# Serial.net
KiCad netlist of a schematic drawn in Altium Designer
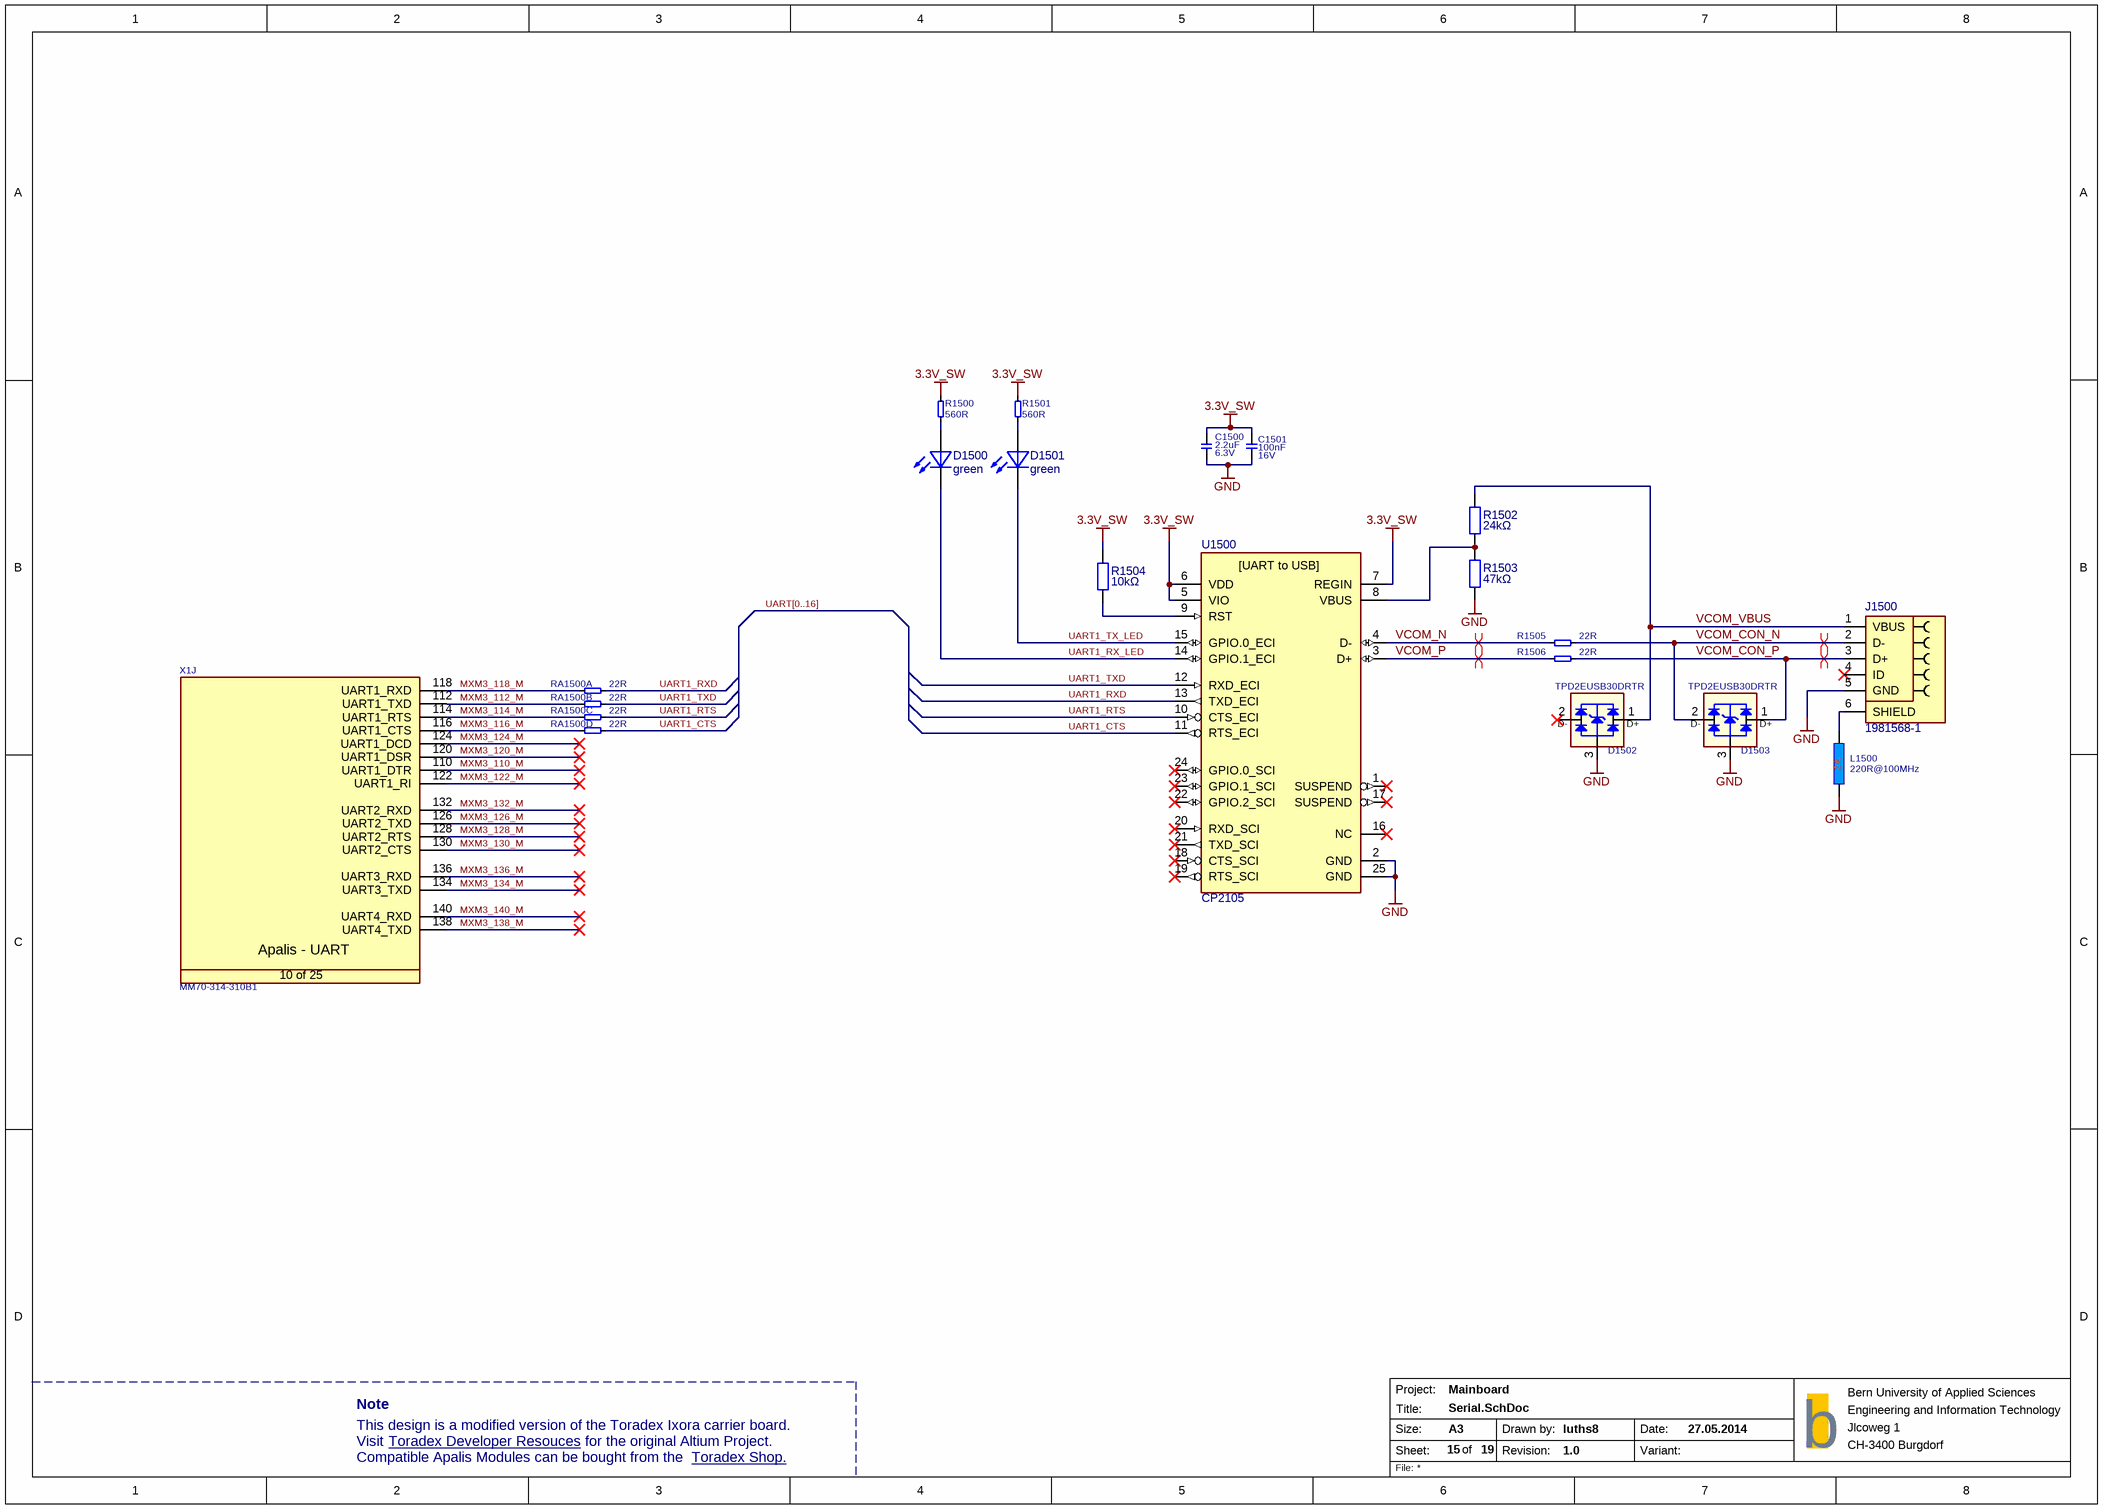
[diagram p0: Serial.SchDoc]

(export (version "E")
  (design (tool "Eeschema 10.0.6"))
  (components
    (comp (ref "C1500")
      (value "2.2uF")
      (footprint "SMD0603CAP")
      (description "Capacitor Ceramic X5R 2.2uF 6.3V 20% 0603")
      (fields (field (name "TOLERANCE") "20%") (field (name "RATING") "6.3V"))
      (libsource (lib "Ixora") (part "C-X5R-2.2uF-6.3V-20%-0603"))
    )
    (comp (ref "C1501")
      (value "100nF")
      (footprint "SMD0603CAP")
      (description "Capacitor Ceramic X7R 100nF 16V 10% 0603")
      (fields (field (name "TOLERANCE") "10%") (field (name "RATING") "16V"))
      (libsource (lib "Ixora") (part "C-X7R-100nF-16V-10%-0402"))
    )
    (comp (ref "D1500")
      (value "green")
      (footprint "LED")
      (description "LED green")
      (fields (field (name "MANUFACTURER PART NO.") "LGM67KG1J224Z"))
      (libsource (lib "Audio-Streamer") (part "LED green"))
    )
    (comp (ref "D1501")
      (value "green")
      (footprint "LED")
      (description "LED green")
      (fields (field (name "MANUFACTURER PART NO.") "LGM67KG1J224Z"))
      (libsource (lib "Audio-Streamer") (part "LED green"))
    )
    (comp (ref "D1502")
      (value "TPD2EUSB30DRTR")
      (footprint "T_TI_TPD2EUSB30DRTR")
      (description "2 Channel Protection for Super Speed USB3.0")
      (fields (field (name "MANUFACTURER PART NO.") "TPD2EUSB30DRTR"))
      (libsource (lib "Ixora") (part "D-TI-TPD2EUSB30DRTR"))
    )
    (comp (ref "D1503")
      (value "TPD2EUSB30DRTR")
      (footprint "T_TI_TPD2EUSB30DRTR")
      (description "2 Channel Protection for Super Speed USB3.0")
      (fields (field (name "MANUFACTURER PART NO.") "TPD2EUSB30DRTR"))
      (libsource (lib "Ixora") (part "D-TI-TPD2EUSB30DRTR"))
    )
    (comp (ref "J1500")
      (value "1981568-1")
      (footprint "HEADER_USB")
      (description "USB Micro Connector")
      (libsource (lib "Audio-Streamer") (part "Connector USB"))
    )
    (comp (ref "L1500")
      (value "220R@100MHz")
      (footprint "INDC1608X95N")
      (description "220R@100MHz 2A EMI FILTER")
      (fields (field (name "TOLERANCE") "25%"))
      (libsource (lib "Ixora") (part "L-220R@100MHz-2A-25%-0603"))
    )
    (comp (ref "R1500")
      (value "560R")
      (footprint "SMD0603RES")
      (description "Resistor 560 ohm 63mW 5% 0603")
      (fields (field (name "TOLERANCE") "5%"))
      (libsource (lib "Ixora") (part "R-560R-63mW-5%-0402"))
    )
    (comp (ref "R1501")
      (value "560R")
      (footprint "SMD0603RES")
      (description "Resistor 560 ohm 63mW 5% 0603")
      (fields (field (name "TOLERANCE") "5%"))
      (libsource (lib "Ixora") (part "R-560R-63mW-5%-0402"))
    )
    (comp (ref "R1502")
      (value "24kΩ")
      (footprint "SMD0603RES")
      (description "Resistor")
      (libsource (lib "Audio-Streamer") (part "Resistor"))
    )
    (comp (ref "R1503")
      (value "47kΩ")
      (footprint "SMD0603RES")
      (description "Resistor")
      (libsource (lib "Audio-Streamer") (part "Resistor"))
    )
    (comp (ref "R1504")
      (value "10kΩ")
      (footprint "SMD0603RES")
      (description "Resistor")
      (libsource (lib "Audio-Streamer") (part "Resistor"))
    )
    (comp (ref "R1505")
      (value "22R")
      (footprint "SMD0603RES")
      (description "Resistor 22 ohm 63mW 5% 0603")
      (fields (field (name "TOLERANCE") "5%"))
      (libsource (lib "Ixora") (part "R-22R-63mW-5%-0402"))
    )
    (comp (ref "R1506")
      (value "22R")
      (footprint "SMD0603RES")
      (description "Resistor 22 ohm 63mW 5% 0603")
      (fields (field (name "TOLERANCE") "5%"))
      (libsource (lib "Ixora") (part "R-22R-63mW-5%-0402"))
    )
    (comp (ref "RA1500")
      (value "22R")
      (footprint "T_Resistor_Array_X4")
      (description "Resistor Array 22 R 63mW 5% 1206")
      (fields (field (name "TOLERANCE") "5%"))
      (libsource (lib "") (part "RA-22R-63mW-5%-1206-div_2"))
    )
    (comp (ref "U1500")
      (value "CP2105")
      (footprint "QFN24")
      (description "USB to UART Bridge")
      (fields (field (name "MANUFACTURER PART NO.") "CP2105-F01-GMR"))
      (libsource (lib "Audio-Streamer") (part "CP2105"))
    )
    (comp (ref "X1")
      (value "CON-JAE-MM70-314-310B1-314-0.5mm")
      (footprint "T_JAE_MM70-314-310B1")
      (description "MXM3 Connector")
      (fields (field (name "MANUFACTURER PART NO.") "MM70-314-310B1"))
      (libsource (lib "Ixora") (part "CON-JAE-MM70-314-310B1-314-0.5mm"))
    )
  )
  (nets
    (net (code "18") (name "/MXM3_110_M") (class "Default")
      (node (ref "X1") (pin "110") (pinfunction "UART1_DTR_110") (pintype "passive+no_connect"))
    )
    (net (code "19") (name "/MXM3_112_M") (class "Default")
      (node (ref "RA1500") (pin "1") (pinfunction "1_1") (pintype "passive"))
      (node (ref "X1") (pin "112") (pinfunction "UART1_TXD_112") (pintype "passive"))
    )
    (net (code "20") (name "/MXM3_114_M") (class "Default")
      (node (ref "RA1500") (pin "2") (pinfunction "2_2") (pintype "passive"))
      (node (ref "X1") (pin "114") (pinfunction "UART1_RTS_114") (pintype "passive"))
    )
    (net (code "22") (name "/MXM3_118_M") (class "Default")
      (node (ref "RA1500") (pin "4") (pinfunction "4_4") (pintype "passive"))
      (node (ref "X1") (pin "118") (pinfunction "UART1_RXD_118") (pintype "passive"))
    )
    (net (code "23") (name "/MXM3_120_M") (class "Default")
      (node (ref "X1") (pin "120") (pinfunction "UART1_DSR_120") (pintype "passive+no_connect"))
    )
    (net (code "24") (name "/MXM3_122_M") (class "Default")
      (node (ref "X1") (pin "122") (pinfunction "UART1_RI_122") (pintype "passive+no_connect"))
    )
    (net (code "25") (name "/MXM3_124_M") (class "Default")
      (node (ref "X1") (pin "124") (pinfunction "UART1_DCD_124") (pintype "passive+no_connect"))
    )
    (net (code "26") (name "/MXM3_126_M") (class "Default")
      (node (ref "X1") (pin "126") (pinfunction "UART2_TXD_126") (pintype "passive+no_connect"))
    )
    (net (code "27") (name "/MXM3_128_M") (class "Default")
      (node (ref "X1") (pin "128") (pinfunction "UART2_RTS_128") (pintype "passive+no_connect"))
    )
    (net (code "28") (name "/MXM3_130_M") (class "Default")
      (node (ref "X1") (pin "130") (pinfunction "UART2_CTS_130") (pintype "passive+no_connect"))
    )
    (net (code "29") (name "/MXM3_132_M") (class "Default")
      (node (ref "X1") (pin "132") (pinfunction "UART2_RXD_132") (pintype "passive+no_connect"))
    )
    (net (code "30") (name "/MXM3_134_M") (class "Default")
      (node (ref "X1") (pin "134") (pinfunction "UART3_TXD_134") (pintype "passive+no_connect"))
    )
    (net (code "31") (name "/MXM3_136_M") (class "Default")
      (node (ref "X1") (pin "136") (pinfunction "UART3_RXD_136") (pintype "passive+no_connect"))
    )
    (net (code "32") (name "/MXM3_138_M") (class "Default")
      (node (ref "X1") (pin "138") (pinfunction "UART4_TXD_138") (pintype "passive+no_connect"))
    )
    (net (code "33") (name "/MXM3_140_M") (class "Default")
      (node (ref "X1") (pin "140") (pinfunction "UART4_RXD_140") (pintype "passive+no_connect"))
    )
    (net (code "34") (name "/UART1_CTS") (class "Default")
      (node (ref "RA1500") (pin "7") (pinfunction "7_7") (pintype "passive"))
      (node (ref "U1500") (pin "11") (pinfunction "RTS_ECI_11") (pintype "output"))
    )
    (net (code "35") (name "/UART1_RTS") (class "Default")
      (node (ref "RA1500") (pin "6") (pinfunction "6_6") (pintype "passive"))
      (node (ref "U1500") (pin "10") (pinfunction "CTS_ECI_10") (pintype "input"))
    )
    (net (code "36") (name "/UART1_RXD") (class "Default")
      (node (ref "RA1500") (pin "8") (pinfunction "8_8") (pintype "passive"))
      (node (ref "U1500") (pin "13") (pinfunction "TXD_ECI_13") (pintype "output"))
    )
    (net (code "37") (name "/UART1_RX_LED") (class "Default")
      (node (ref "D1500") (pin "C") (pinfunction "C_C") (pintype "passive"))
      (node (ref "U1500") (pin "14") (pinfunction "GPIO.1_ECI_14") (pintype "bidirectional"))
    )
    (net (code "38") (name "/UART1_TXD") (class "Default")
      (node (ref "RA1500") (pin "5") (pinfunction "5_5") (pintype "passive"))
      (node (ref "U1500") (pin "12") (pinfunction "RXD_ECI_12") (pintype "input"))
    )
    (net (code "39") (name "/UART1_TX_LED") (class "Default")
      (node (ref "D1501") (pin "C") (pinfunction "C_C") (pintype "passive"))
      (node (ref "U1500") (pin "15") (pinfunction "GPIO.0_ECI_15") (pintype "bidirectional"))
    )
    (net (code "41") (name "/VCOM_CON_N") (class "Default")
      (node (ref "D1503") (pin "2") (pinfunction "D-_2") (pintype "power_in"))
      (node (ref "J1500") (pin "2") (pinfunction "D-_2") (pintype "passive"))
      (node (ref "R1505") (pin "2") (pinfunction "2_2") (pintype "passive"))
    )
    (net (code "42") (name "/VCOM_CON_P") (class "Default")
      (node (ref "D1503") (pin "1") (pinfunction "D+_1") (pintype "power_in"))
      (node (ref "J1500") (pin "3") (pinfunction "D+_3") (pintype "passive"))
      (node (ref "R1506") (pin "2") (pinfunction "2_2") (pintype "passive"))
    )
    (net (code "43") (name "/VCOM_N") (class "Default")
      (node (ref "R1505") (pin "1") (pinfunction "1_1") (pintype "passive"))
      (node (ref "U1500") (pin "4") (pinfunction "D-_4") (pintype "bidirectional"))
    )
    (net (code "44") (name "/VCOM_P") (class "Default")
      (node (ref "R1506") (pin "1") (pinfunction "1_1") (pintype "passive"))
      (node (ref "U1500") (pin "3") (pinfunction "D+_3") (pintype "bidirectional"))
    )
    (net (code "45") (name "/VCOM_VBUS") (class "Default")
      (node (ref "D1502") (pin "1") (pinfunction "D+_1") (pintype "power_in"))
      (node (ref "J1500") (pin "1") (pinfunction "VBUS_1") (pintype "passive"))
      (node (ref "R1502") (pin "2") (pinfunction "2_2") (pintype "passive"))
    )
    (net (code "46") (name "3.3V_SW") (class "Default")
      (node (ref "C1500") (pin "2") (pinfunction "2_2") (pintype "passive"))
      (node (ref "C1501") (pin "2") (pinfunction "2_2") (pintype "passive"))
      (node (ref "R1500") (pin "1") (pinfunction "1_1") (pintype "passive"))
      (node (ref "R1501") (pin "1") (pinfunction "1_1") (pintype "passive"))
      (node (ref "R1504") (pin "2") (pinfunction "2_2") (pintype "passive"))
      (node (ref "U1500") (pin "5") (pinfunction "VIO_5") (pintype "power_in"))
      (node (ref "U1500") (pin "6") (pinfunction "VDD_6") (pintype "power_in"))
      (node (ref "U1500") (pin "7") (pinfunction "REGIN_7") (pintype "power_in"))
    )
    (net (code "47") (name "GND") (class "Default")
      (node (ref "C1500") (pin "1") (pinfunction "1_1") (pintype "passive"))
      (node (ref "C1501") (pin "1") (pinfunction "1_1") (pintype "passive"))
      (node (ref "D1502") (pin "3") (pinfunction "3_3") (pintype "power_in"))
      (node (ref "D1503") (pin "3") (pinfunction "3_3") (pintype "power_in"))
      (node (ref "J1500") (pin "5") (pinfunction "GND_5") (pintype "passive"))
      (node (ref "L1500") (pin "1") (pinfunction "1_1") (pintype "passive"))
      (node (ref "R1503") (pin "1") (pinfunction "1_1") (pintype "passive"))
      (node (ref "U1500") (pin "2") (pinfunction "GND_2") (pintype "power_in"))
      (node (ref "U1500") (pin "25") (pinfunction "GND_25") (pintype "power_in"))
    )
    (net (code "48") (name "Net-(D1500-PadA)") (class "Default")
      (node (ref "D1500") (pin "A") (pinfunction "A_A") (pintype "passive"))
      (node (ref "R1500") (pin "2") (pinfunction "2_2") (pintype "passive"))
    )
    (net (code "49") (name "Net-(D1501-PadA)") (class "Default")
      (node (ref "D1501") (pin "A") (pinfunction "A_A") (pintype "passive"))
      (node (ref "R1501") (pin "2") (pinfunction "2_2") (pintype "passive"))
    )
    (net (code "50") (name "Net-(J1500-SHIELD)") (class "Default")
      (node (ref "J1500") (pin "6") (pinfunction "SHIELD_6") (pintype "passive"))
      (node (ref "L1500") (pin "2") (pinfunction "2_2") (pintype "passive"))
    )
    (net (code "51") (name "Net-(U1500-RST)") (class "Default")
      (node (ref "R1504") (pin "1") (pinfunction "1_1") (pintype "passive"))
      (node (ref "U1500") (pin "9") (pinfunction "RST_9") (pintype "input"))
    )
    (net (code "52") (name "Net-(U1500-VBUS)") (class "Default")
      (node (ref "R1502") (pin "1") (pinfunction "1_1") (pintype "passive"))
      (node (ref "R1503") (pin "2") (pinfunction "2_2") (pintype "passive"))
      (node (ref "U1500") (pin "8") (pinfunction "VBUS_8") (pintype "power_in"))
    )
    (net (code "53") (name "Net-(X1J-UART1_CTS)") (class "Default")
      (node (ref "RA1500") (pin "3") (pinfunction "3_3") (pintype "passive"))
      (node (ref "X1") (pin "116") (pinfunction "UART1_CTS_116") (pintype "passive"))
    )
    (net (code "54") (name "unconnected-(D1502-D--Pad2)") (class "Default")
      (node (ref "D1502") (pin "2") (pinfunction "D-_2") (pintype "power_in+no_connect"))
    )
    (net (code "55") (name "unconnected-(J1500-ID-Pad4)") (class "Default")
      (node (ref "J1500") (pin "4") (pinfunction "ID_4") (pintype "passive+no_connect"))
    )
    (net (code "56") (name "unconnected-(U1500-CTS_SCI-Pad18)") (class "Default")
      (node (ref "U1500") (pin "18") (pinfunction "CTS_SCI_18") (pintype "input+no_connect"))
    )
    (net (code "57") (name "unconnected-(U1500-GPIO.0_SCI-Pad24)") (class "Default")
      (node (ref "U1500") (pin "24") (pinfunction "GPIO.0_SCI_24") (pintype "bidirectional+no_connect"))
    )
    (net (code "58") (name "unconnected-(U1500-GPIO.1_SCI-Pad23)") (class "Default")
      (node (ref "U1500") (pin "23") (pinfunction "GPIO.1_SCI_23") (pintype "bidirectional+no_connect"))
    )
    (net (code "59") (name "unconnected-(U1500-GPIO.2_SCI-Pad22)") (class "Default")
      (node (ref "U1500") (pin "22") (pinfunction "GPIO.2_SCI_22") (pintype "bidirectional+no_connect"))
    )
    (net (code "60") (name "unconnected-(U1500-NC-Pad16)") (class "Default")
      (node (ref "U1500") (pin "16") (pinfunction "NC_16") (pintype "passive+no_connect"))
    )
    (net (code "61") (name "unconnected-(U1500-RTS_SCI-Pad19)") (class "Default")
      (node (ref "U1500") (pin "19") (pinfunction "RTS_SCI_19") (pintype "output+no_connect"))
    )
    (net (code "62") (name "unconnected-(U1500-RXD_SCI-Pad20)") (class "Default")
      (node (ref "U1500") (pin "20") (pinfunction "RXD_SCI_20") (pintype "input+no_connect"))
    )
    (net (code "63") (name "unconnected-(U1500-SUSPEND-Pad1)") (class "Default")
      (node (ref "U1500") (pin "1") (pinfunction "SUSPEND_1") (pintype "output+no_connect"))
    )
    (net (code "64") (name "unconnected-(U1500-SUSPEND-Pad17)") (class "Default")
      (node (ref "U1500") (pin "17") (pinfunction "SUSPEND_17") (pintype "output+no_connect"))
    )
    (net (code "65") (name "unconnected-(U1500-TXD_SCI-Pad21)") (class "Default")
      (node (ref "U1500") (pin "21") (pinfunction "TXD_SCI_21") (pintype "output+no_connect"))
    )
  )
)
